# teensy.net
KiCad netlist of a schematic drawn in Altium Designer
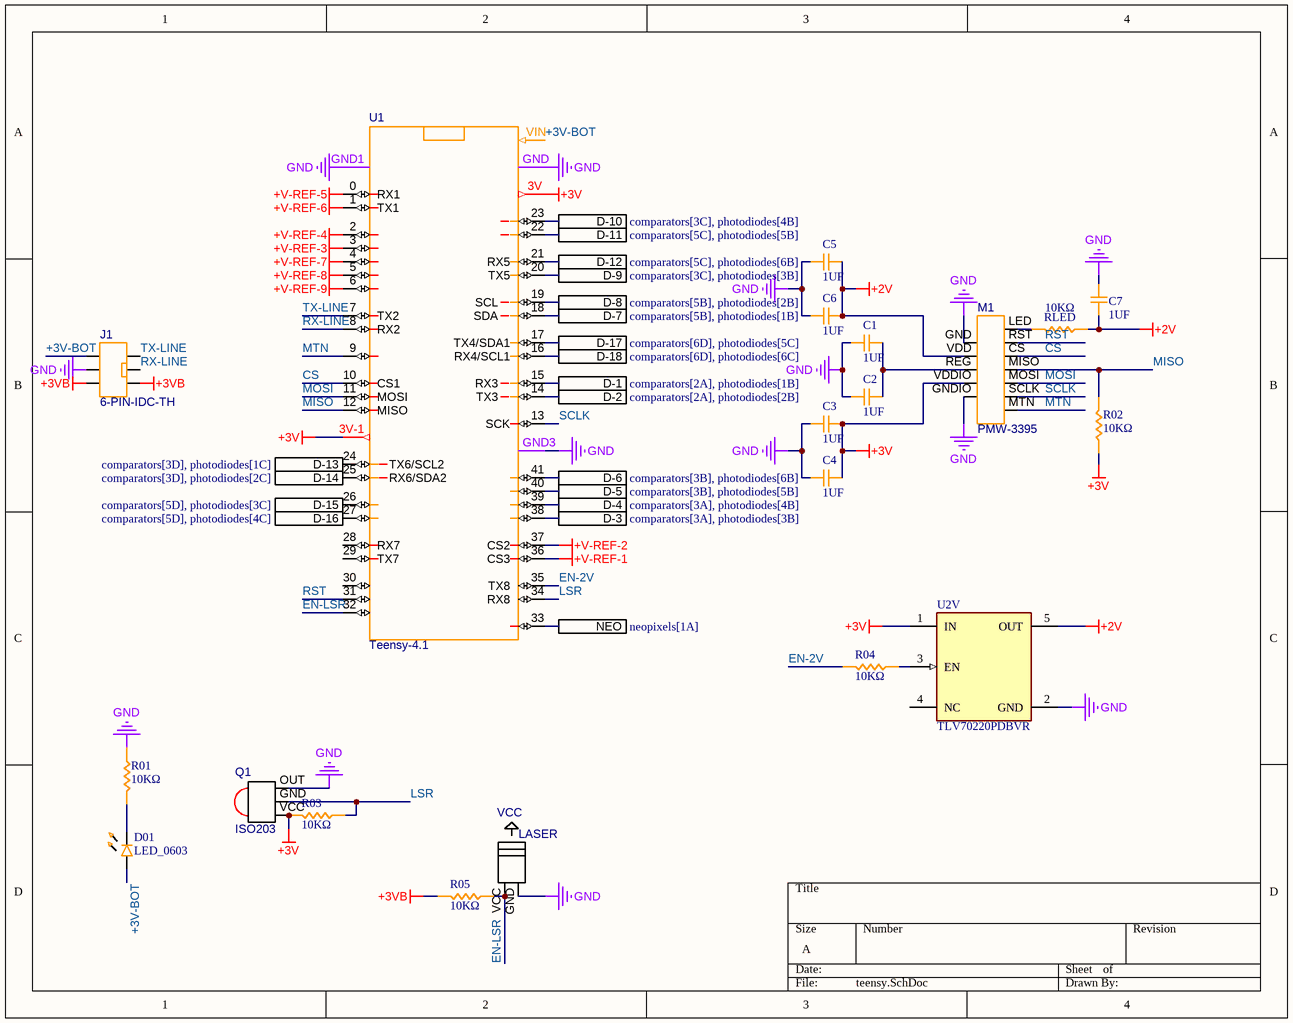
[diagram p0: teensy.SchDoc]

(export (version "E")
  (design (tool "Eeschema 10.0.6"))
  (components
    (comp (ref "C1")
      (value "1UF")
      (footprint "CAP_0603")
      (description "Capacitor SMD 0603 generic")
      (libsource (lib "RC") (part "CAP_0603"))
    )
    (comp (ref "C2")
      (value "1UF")
      (footprint "CAP_0603")
      (description "Capacitor SMD 0603 generic")
      (libsource (lib "RC") (part "CAP_0603"))
    )
    (comp (ref "C3")
      (value "1UF")
      (footprint "CAP_0603")
      (description "Capacitor SMD 0603 generic")
      (libsource (lib "RC") (part "CAP_0603"))
    )
    (comp (ref "C4")
      (value "1UF")
      (footprint "CAP_0603")
      (description "Capacitor SMD 0603 generic")
      (libsource (lib "RC") (part "CAP_0603"))
    )
    (comp (ref "C5")
      (value "1UF")
      (footprint "CAP_0603")
      (description "Capacitor SMD 0603 generic")
      (libsource (lib "RC") (part "CAP_0603"))
    )
    (comp (ref "C6")
      (value "1UF")
      (footprint "CAP_0603")
      (description "Capacitor SMD 0603 generic")
      (libsource (lib "RC") (part "CAP_0603"))
    )
    (comp (ref "C7")
      (value "1UF")
      (footprint "CAP_0603")
      (description "Capacitor SMD 0603 generic")
      (libsource (lib "RC") (part "CAP_0603"))
    )
    (comp (ref "D01") (value "LED_0603") (footprint "LED_0603") (libsource (lib "RC") (part "LED_0603")))
    (comp (ref "J1")
      (value "6-PIN-IDC-TH")
      (footprint "6-PIN-IDC-TH")
      (libsource (lib "RC") (part "6-PIN-IDC-TH"))
    )
    (comp (ref "M1") (value "PMW-3395") (footprint "MOUSE-DIP16") (libsource (lib "RC") (part "PMW-3395")))
    (comp (ref "Q1") (value "ISO203") (footprint "TSSP-58038") (libsource (lib "RC") (part "TSSP-58038")))
    (comp (ref "R01")
      (value "10KΩ")
      (footprint "RES_0603")
      (description "Resistor SMD 0603 generic")
      (libsource (lib "RC") (part "RES_0603"))
    )
    (comp (ref "R02")
      (value "10KΩ")
      (footprint "RES_0603")
      (description "Resistor SMD 0603 generic")
      (libsource (lib "RC") (part "RES_0603"))
    )
    (comp (ref "R03")
      (value "10KΩ")
      (footprint "RES_0603")
      (description "Resistor SMD 0603 generic")
      (libsource (lib "RC") (part "RES_0603"))
    )
    (comp (ref "R04")
      (value "10KΩ")
      (footprint "RES_0603")
      (description "Resistor SMD 0603 generic")
      (libsource (lib "RC") (part "RES_0603"))
    )
    (comp (ref "R05")
      (value "10KΩ")
      (footprint "RES_0603")
      (description "Resistor SMD 0603 generic")
      (libsource (lib "RC") (part "RES_0603"))
    )
    (comp (ref "RLED")
      (value "10KΩ")
      (footprint "RES_0603")
      (description "Resistor SMD 0603 generic")
      (libsource (lib "RC") (part "RES_0603"))
    )
    (comp (ref "U1") (value "Teensy-4.1") (footprint "Teensy-4.1") (libsource (lib "RC") (part "Teensy-4.1")))
    (comp (ref "U2V")
      (value "TLV70220PDBVR")
      (footprint "FP-DBV0005A-MFG")
      (description "IC REG LINEAR 2V 300MA SOT23-5")
      (fields
        (field (name "OCTOPART") "https://octopart.com/tlv70220pdbvr-texas+instruments-20023687")
        (field (name "MANUFACTURER") "Texas Instruments")
      )
      (libsource (lib "Altium Content Vault") (part "3ee2588bdf7704766daa760b4559fef"))
    )
    (comp (ref "VCC") (value "LASER") (footprint "LASER") (libsource (lib "RC") (part "LASER")))
  )
  (nets
    (net (code "1") (name "+2V") (class "Default")
      (node (ref "C5") (pin "1") (pintype "passive"))
      (node (ref "C6") (pin "1") (pintype "passive"))
      (node (ref "C7") (pin "1") (pintype "passive"))
      (node (ref "M1") (pin "VDD") (pintype "passive"))
      (node (ref "RLED") (pin "2") (pintype "passive"))
      (node (ref "U2V") (pin "5") (pinfunction "OUT_5") (pintype "power_in"))
    )
    (net (code "2") (name "+3V") (class "Default")
      (node (ref "C3") (pin "2") (pintype "passive"))
      (node (ref "C4") (pin "2") (pintype "passive"))
      (node (ref "M1") (pin "VDDIO") (pintype "passive"))
      (node (ref "Q1") (pin "VCC") (pintype "passive"))
      (node (ref "R02") (pin "2") (pintype "passive"))
      (node (ref "R03") (pin "1") (pintype "passive"))
      (node (ref "U1") (pin "3V") (pintype "output"))
      (node (ref "U1") (pin "3V-1") (pintype "output"))
      (node (ref "U2V") (pin "1") (pinfunction "IN_1") (pintype "power_in"))
    )
    (net (code "3") (name "+3VB") (class "Default")
      (node (ref "J1") (pin "3") (pintype "passive"))
      (node (ref "J1") (pin "4") (pintype "passive"))
      (node (ref "R05") (pin "1") (pintype "passive"))
    )
    (net (code "4") (name "+V-REF-1") (class "Default")
      (node (ref "U1") (pin "36") (pinfunction "CS3_36") (pintype "bidirectional"))
    )
    (net (code "5") (name "+V-REF-2") (class "Default")
      (node (ref "U1") (pin "37") (pinfunction "CS2_37") (pintype "bidirectional"))
    )
    (net (code "6") (name "+V-REF-3") (class "Default") (node (ref "U1") (pin "3") (pintype "bidirectional")))
    (net (code "7") (name "+V-REF-4") (class "Default") (node (ref "U1") (pin "2") (pintype "bidirectional")))
    (net (code "8") (name "+V-REF-5") (class "Default")
      (node (ref "U1") (pin "0") (pinfunction "RX1_0") (pintype "bidirectional"))
    )
    (net (code "9") (name "+V-REF-6") (class "Default")
      (node (ref "U1") (pin "1") (pinfunction "TX1_1") (pintype "bidirectional"))
    )
    (net (code "10") (name "+V-REF-7") (class "Default")
      (node (ref "U1") (pin "4") (pintype "bidirectional"))
    )
    (net (code "11") (name "+V-REF-8") (class "Default")
      (node (ref "U1") (pin "5") (pintype "bidirectional"))
    )
    (net (code "12") (name "+V-REF-9") (class "Default")
      (node (ref "U1") (pin "6") (pintype "bidirectional"))
    )
    (net (code "13") (name "/+3V-BOT") (class "Default")
      (node (ref "D01") (pin "A") (pinfunction "2_A") (pintype "passive"))
      (node (ref "J1") (pin "1") (pintype "passive"))
      (node (ref "U1") (pin "VIN") (pintype "input"))
    )
    (net (code "14") (name "/CS") (class "Default")
      (node (ref "M1") (pin "CS") (pintype "passive"))
      (node (ref "U1") (pin "10") (pinfunction "CS1_10") (pintype "bidirectional"))
    )
    (net (code "15") (name "/D-1") (class "Default")
      (node (ref "U1") (pin "15") (pinfunction "RX3_15") (pintype "bidirectional"))
    )
    (net (code "16") (name "/D-2") (class "Default")
      (node (ref "U1") (pin "14") (pinfunction "TX3_14") (pintype "bidirectional"))
    )
    (net (code "17") (name "/D-3") (class "Default") (node (ref "U1") (pin "38") (pintype "bidirectional")))
    (net (code "18") (name "/D-4") (class "Default") (node (ref "U1") (pin "39") (pintype "bidirectional")))
    (net (code "19") (name "/D-5") (class "Default") (node (ref "U1") (pin "40") (pintype "bidirectional")))
    (net (code "20") (name "/D-6") (class "Default") (node (ref "U1") (pin "41") (pintype "bidirectional")))
    (net (code "21") (name "/D-7") (class "Default")
      (node (ref "U1") (pin "18") (pinfunction "SDA_18") (pintype "bidirectional"))
    )
    (net (code "22") (name "/D-8") (class "Default")
      (node (ref "U1") (pin "19") (pinfunction "SCL_19") (pintype "bidirectional"))
    )
    (net (code "23") (name "/D-9") (class "Default")
      (node (ref "U1") (pin "20") (pinfunction "TX5_20") (pintype "bidirectional"))
    )
    (net (code "24") (name "/D-10") (class "Default") (node (ref "U1") (pin "23") (pintype "bidirectional")))
    (net (code "25") (name "/D-11") (class "Default") (node (ref "U1") (pin "22") (pintype "bidirectional")))
    (net (code "26") (name "/D-12") (class "Default")
      (node (ref "U1") (pin "21") (pinfunction "RX5_21") (pintype "bidirectional"))
    )
    (net (code "27") (name "/D-13") (class "Default")
      (node (ref "U1") (pin "24") (pinfunction "TX6/SCL2_24") (pintype "bidirectional"))
    )
    (net (code "28") (name "/D-14") (class "Default")
      (node (ref "U1") (pin "25") (pinfunction "RX6/SDA2_25") (pintype "bidirectional"))
    )
    (net (code "29") (name "/D-15") (class "Default") (node (ref "U1") (pin "26") (pintype "bidirectional")))
    (net (code "30") (name "/D-16") (class "Default") (node (ref "U1") (pin "27") (pintype "bidirectional")))
    (net (code "31") (name "/D-17") (class "Default")
      (node (ref "U1") (pin "17") (pinfunction "TX4/SDA1_17") (pintype "bidirectional"))
    )
    (net (code "32") (name "/D-18") (class "Default")
      (node (ref "U1") (pin "16") (pinfunction "RX4/SCL1_16") (pintype "bidirectional"))
    )
    (net (code "33") (name "/EN-2V") (class "Default")
      (node (ref "R04") (pin "1") (pintype "passive"))
      (node (ref "U1") (pin "35") (pinfunction "TX8_35") (pintype "bidirectional"))
    )
    (net (code "34") (name "/EN-LSR") (class "Default")
      (node (ref "R05") (pin "2") (pintype "passive"))
      (node (ref "U1") (pin "32") (pintype "bidirectional"))
      (node (ref "VCC") (pin "VCC") (pintype "passive"))
    )
    (net (code "35") (name "/LSR") (class "Default")
      (node (ref "Q1") (pin "GND") (pintype "passive"))
      (node (ref "R03") (pin "2") (pintype "passive"))
      (node (ref "U1") (pin "34") (pinfunction "RX8_34") (pintype "bidirectional"))
    )
    (net (code "36") (name "/MISO") (class "Default")
      (node (ref "M1") (pin "MISO") (pintype "passive"))
      (node (ref "R02") (pin "1") (pintype "passive"))
      (node (ref "U1") (pin "12") (pinfunction "MISO_12") (pintype "bidirectional"))
    )
    (net (code "37") (name "/MOSI") (class "Default")
      (node (ref "M1") (pin "MOSI") (pintype "passive"))
      (node (ref "U1") (pin "11") (pinfunction "MOSI_11") (pintype "bidirectional"))
    )
    (net (code "38") (name "/MTN") (class "Default")
      (node (ref "M1") (pin "MTN") (pintype "passive"))
      (node (ref "U1") (pin "9") (pintype "bidirectional"))
    )
    (net (code "39") (name "/NEO") (class "Default") (node (ref "U1") (pin "33") (pintype "bidirectional")))
    (net (code "40") (name "/RST") (class "Default")
      (node (ref "M1") (pin "RST") (pintype "passive"))
      (node (ref "U1") (pin "31") (pintype "bidirectional"))
    )
    (net (code "41") (name "/RX-LINE") (class "Default")
      (node (ref "J1") (pin "5") (pintype "passive"))
      (node (ref "U1") (pin "8") (pinfunction "RX2_8") (pintype "bidirectional"))
    )
    (net (code "42") (name "/SCLK") (class "Default")
      (node (ref "M1") (pin "SCLK") (pintype "passive"))
      (node (ref "U1") (pin "13") (pinfunction "SCK_13") (pintype "bidirectional"))
    )
    (net (code "43") (name "/TX-LINE") (class "Default")
      (node (ref "J1") (pin "6") (pintype "passive"))
      (node (ref "U1") (pin "7") (pinfunction "TX2_7") (pintype "bidirectional"))
    )
    (net (code "44") (name "GND") (class "Default")
      (node (ref "C1") (pin "1") (pintype "passive"))
      (node (ref "C2") (pin "1") (pintype "passive"))
      (node (ref "C3") (pin "1") (pintype "passive"))
      (node (ref "C4") (pin "1") (pintype "passive"))
      (node (ref "C5") (pin "2") (pintype "passive"))
      (node (ref "C6") (pin "2") (pintype "passive"))
      (node (ref "C7") (pin "2") (pintype "passive"))
      (node (ref "J1") (pin "2") (pintype "passive"))
      (node (ref "M1") (pin "GND") (pintype "passive"))
      (node (ref "M1") (pin "GNDIO") (pintype "passive"))
      (node (ref "Q1") (pin "OUT") (pintype "passive"))
      (node (ref "R01") (pin "2") (pintype "passive"))
      (node (ref "U1") (pin "GND") (pintype "passive"))
      (node (ref "U1") (pin "GND1") (pintype "passive"))
      (node (ref "U1") (pin "GND3") (pintype "power_in"))
      (node (ref "U2V") (pin "2") (pinfunction "GND_2") (pintype "power_in"))
      (node (ref "VCC") (pin "GND") (pintype "passive"))
    )
    (net (code "45") (name "Net-(C1-Pad2)") (class "Default")
      (node (ref "C1") (pin "2") (pintype "passive"))
      (node (ref "C2") (pin "2") (pintype "passive"))
      (node (ref "M1") (pin "REG") (pintype "passive"))
    )
    (net (code "46") (name "Net-(D01-1)") (class "Default")
      (node (ref "D01") (pin "C") (pinfunction "1_C") (pintype "passive"))
      (node (ref "R01") (pin "1") (pintype "passive"))
    )
    (net (code "47") (name "Net-(M1-PadLED)") (class "Default")
      (node (ref "M1") (pin "LED") (pintype "passive"))
      (node (ref "RLED") (pin "1") (pintype "passive"))
    )
    (net (code "48") (name "Net-(U2V-EN)") (class "Default")
      (node (ref "R04") (pin "2") (pintype "passive"))
      (node (ref "U2V") (pin "3") (pinfunction "EN_3") (pintype "input"))
    )
    (net (code "49") (name "unconnected-(U1-Pad30)") (class "Default")
      (node (ref "U1") (pin "30") (pintype "bidirectional"))
    )
    (net (code "50") (name "unconnected-(U1-RX7-Pad28)") (class "Default")
      (node (ref "U1") (pin "28") (pinfunction "RX7_28") (pintype "bidirectional"))
    )
    (net (code "51") (name "unconnected-(U1-TX7-Pad29)") (class "Default")
      (node (ref "U1") (pin "29") (pinfunction "TX7_29") (pintype "bidirectional"))
    )
    (net (code "52") (name "unconnected-(U2V-NC-Pad4)") (class "Default")
      (node (ref "U2V") (pin "4") (pinfunction "NC_4") (pintype "passive"))
    )
  )
)
